# board.net
KiCad netlist of a schematic drawn in EAGLE
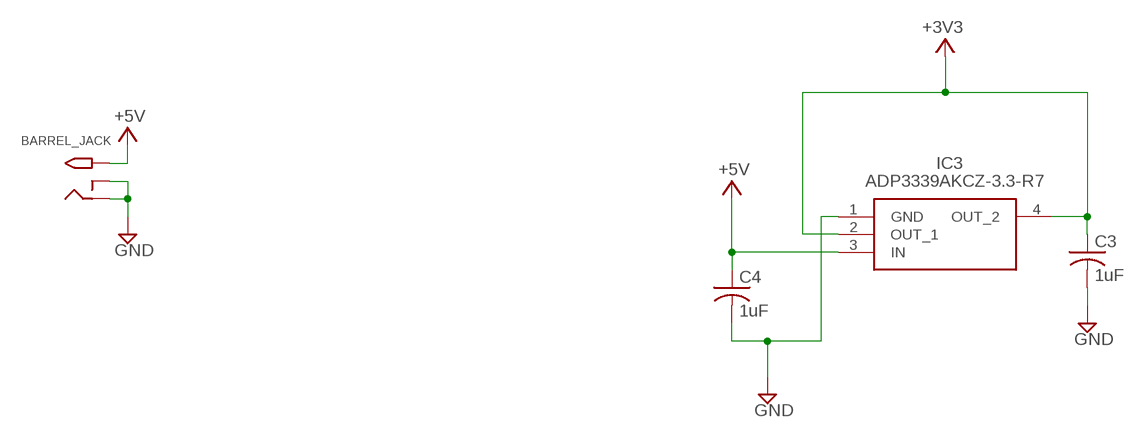
[diagram p0: schematic, sheet 1]
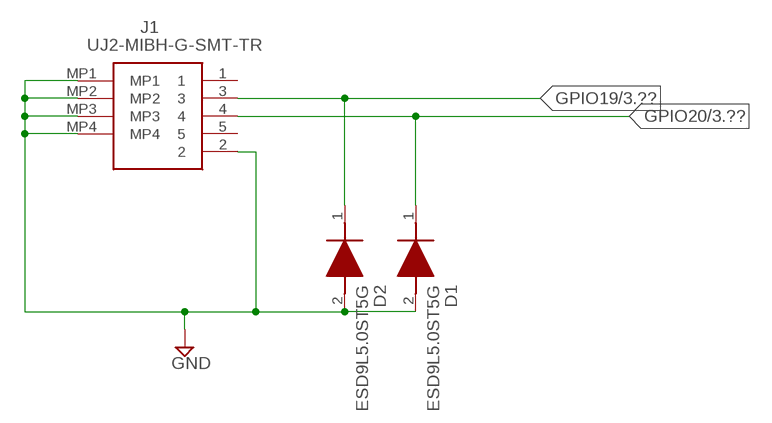
[diagram p1: schematic, sheet 2]
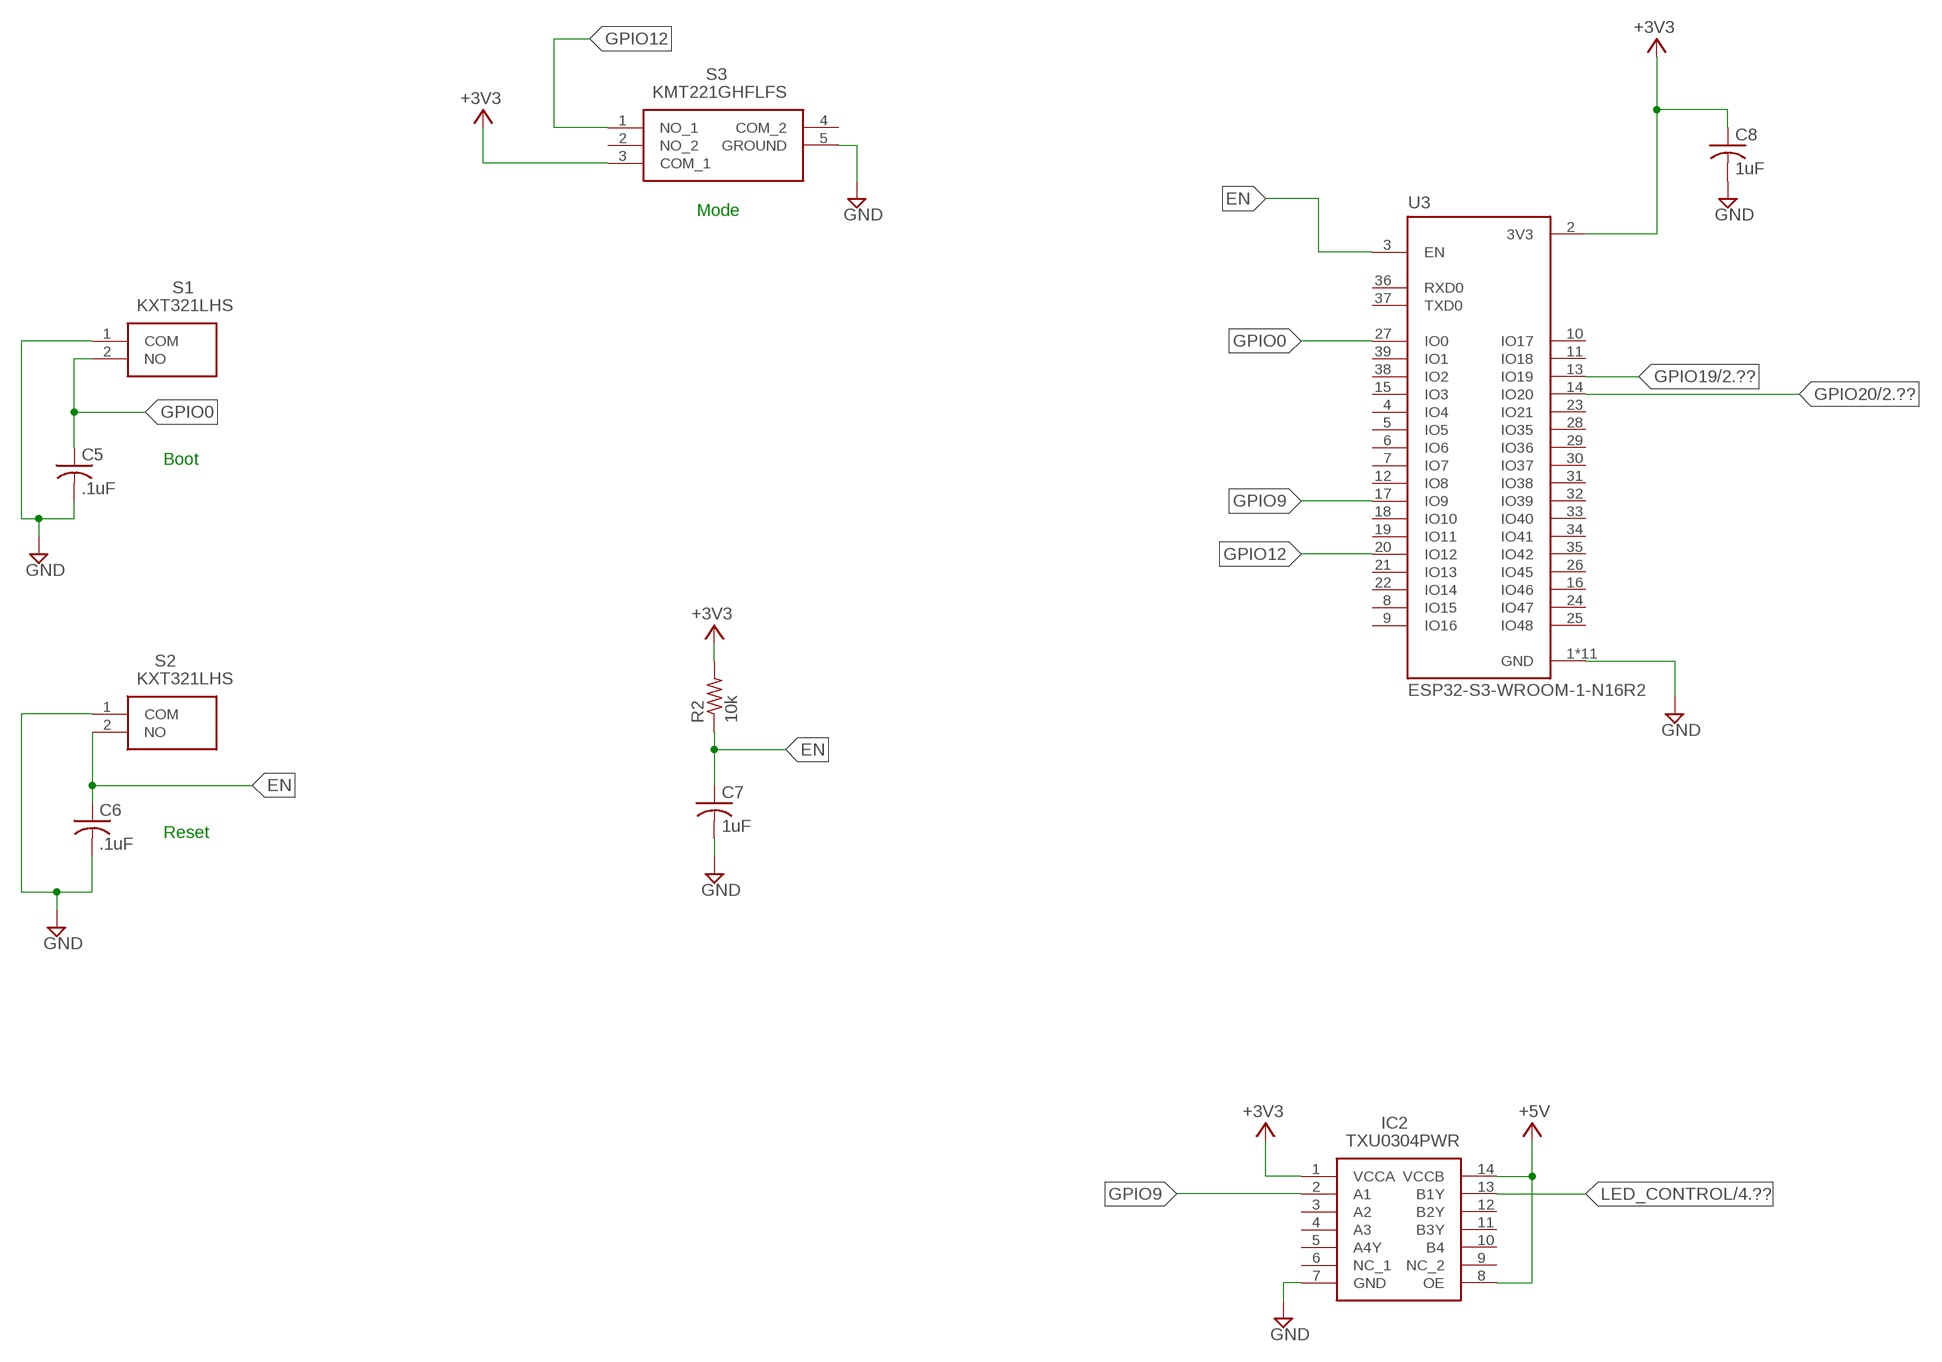
[diagram p2: schematic, sheet 3]
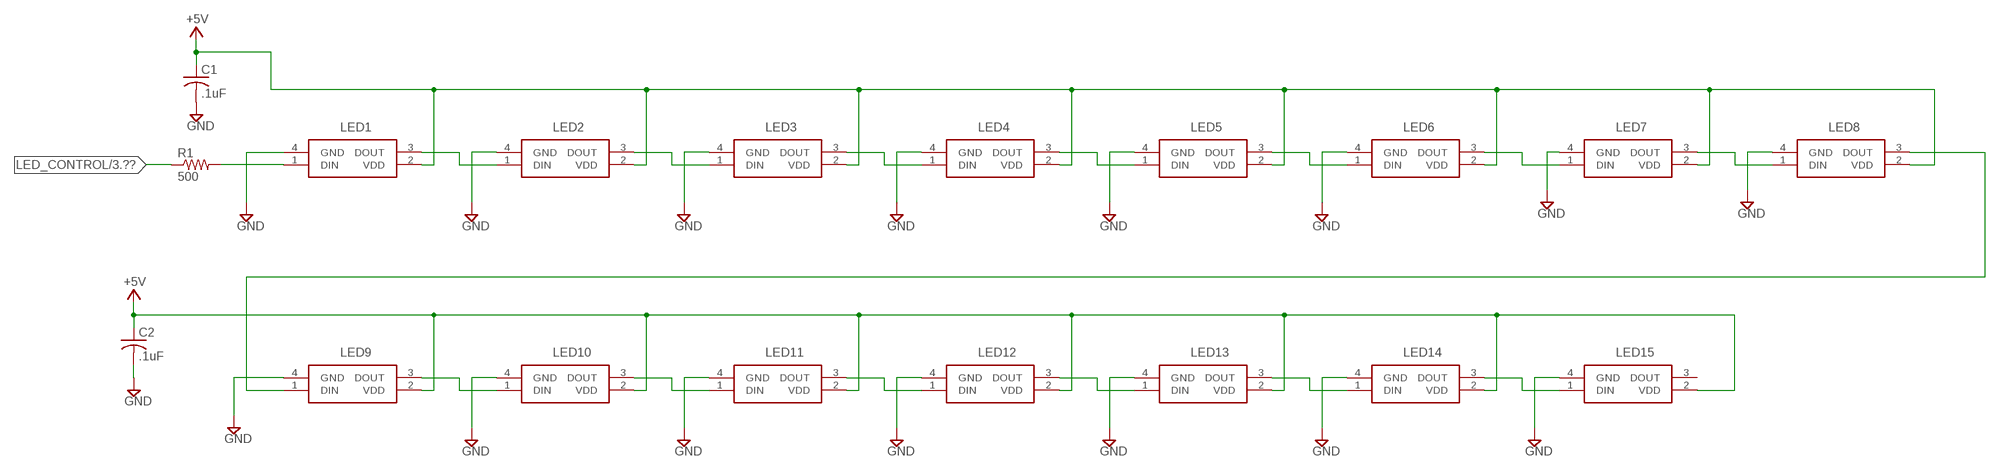
[diagram p3: schematic, sheet 4]
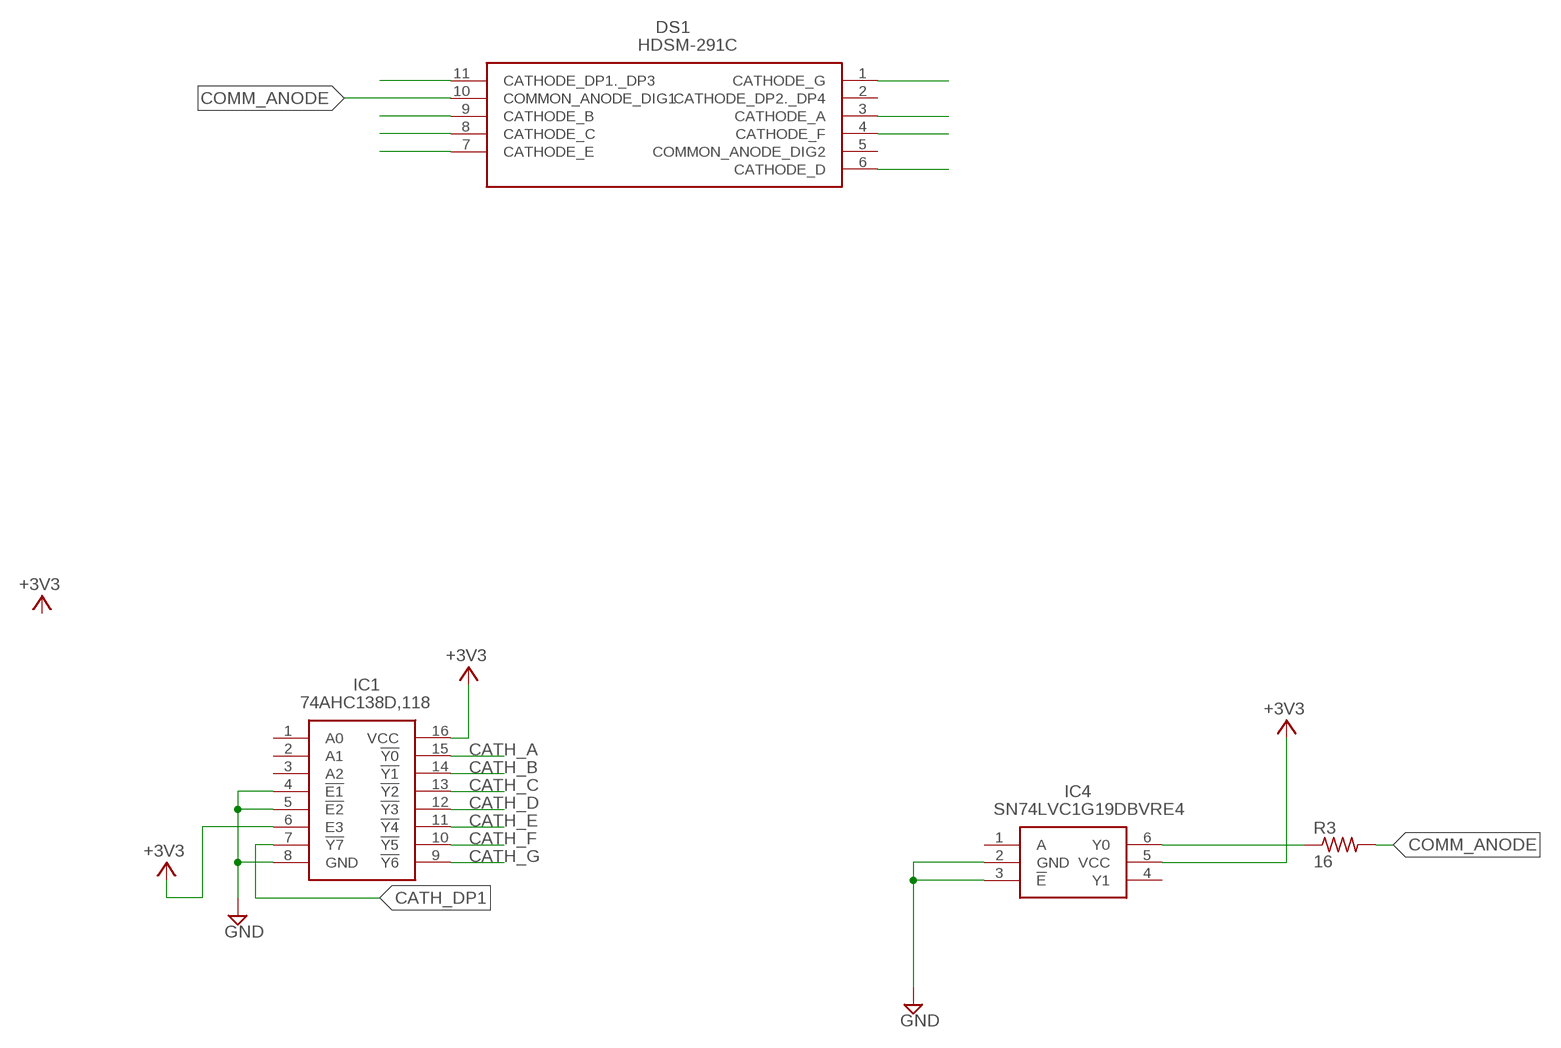
[diagram p4: schematic, sheet 5]

(export (version "E")
  (design (tool "Eeschema 10.0.6"))
  (components
    (comp (ref "BARREL_JACK")
      (value "2.1MMJACKTHM")
      (footprint "eagle-import:PJ-102A")
      (libsource (lib "eagle-import") (part "2.1MMJACKTHM"))
    )
    (comp (ref "C3")
      (value "1uF")
      (footprint "eagle-import:C0402")
      (libsource (lib "eagle-import") (part "C-USC0402"))
    )
    (comp (ref "C4")
      (value "1uF")
      (footprint "eagle-import:C0402")
      (libsource (lib "eagle-import") (part "C-USC0402"))
    )
    (comp (ref "IC3")
      (value "ADP3339AKCZ-3.3-R7")
      (footprint "eagle-import:SOT230P700X180-4N")
      (fields (field (name "MOUSER_PART_NUMBER") "584-ADP3339AKCZ3.3R7"))
      (libsource (lib "eagle-import") (part "ADP3339AKCZ-3.3-R7"))
    )
    (comp (ref "D1")
      (value "ESD9L5.0ST5G")
      (footprint "eagle-import:SODFL1006X40N")
      (fields (field (name "MOUSER_PART_NUMBER") "863-ESD9L5.0ST5G"))
      (libsource (lib "eagle-import") (part "ESD9L5.0ST5G"))
    )
    (comp (ref "D2")
      (value "ESD9L5.0ST5G")
      (footprint "eagle-import:SODFL1006X40N")
      (fields (field (name "MOUSER_PART_NUMBER") "863-ESD9L5.0ST5G"))
      (libsource (lib "eagle-import") (part "ESD9L5.0ST5G"))
    )
    (comp (ref "J1")
      (value "UJ2-MIBH-G-SMT-TR")
      (footprint "eagle-import:UJ2MIBHGSMTTR")
      (fields (field (name "MOUSER_PART_NUMBER") "490-UJ2-MIBH-G-SMTTR"))
      (libsource (lib "eagle-import") (part "UJ2-MIBH-G-SMT-TR"))
    )
    (comp (ref "C5")
      (value ".1uF")
      (footprint "eagle-import:C0402")
      (libsource (lib "eagle-import") (part "C-USC0402"))
    )
    (comp (ref "C6")
      (value ".1uF")
      (footprint "eagle-import:C0402")
      (libsource (lib "eagle-import") (part "C-USC0402"))
    )
    (comp (ref "C7")
      (value "1uF")
      (footprint "eagle-import:C0402")
      (libsource (lib "eagle-import") (part "C-USC0402"))
    )
    (comp (ref "C8")
      (value "1uF")
      (footprint "eagle-import:C0402")
      (libsource (lib "eagle-import") (part "C-USC0402"))
    )
    (comp (ref "IC2")
      (value "TXU0304PWR")
      (footprint "eagle-import:SOP65P640X120-14N")
      (fields (field (name "MOUSER_PART_NUMBER") "595-TXU0304PWR"))
      (libsource (lib "eagle-import") (part "TXU0304PWR"))
    )
    (comp (ref "R2")
      (value "10k")
      (footprint "eagle-import:R0402")
      (libsource (lib "eagle-import") (part "R-US_R0402"))
    )
    (comp (ref "S1")
      (value "KXT321LHS")
      (footprint "eagle-import:KXT321LHS")
      (fields (field (name "MOUSER_PART_NUMBER") "611-KXT321LHS"))
      (libsource (lib "eagle-import") (part "KXT321LHS"))
    )
    (comp (ref "S2")
      (value "KXT321LHS")
      (footprint "eagle-import:KXT321LHS")
      (fields (field (name "MOUSER_PART_NUMBER") "611-KXT321LHS"))
      (libsource (lib "eagle-import") (part "KXT321LHS"))
    )
    (comp (ref "S3")
      (value "KMT221GHFLFS")
      (footprint "eagle-import:KMT221GHFLFS")
      (fields (field (name "MOUSER_PART_NUMBER") "611-KMT221GHFLFS"))
      (libsource (lib "eagle-import") (part "KMT221GHFLFS"))
    )
    (comp (ref "U3")
      (value "ESP32-S3-WROOM-1-N16R2")
      (footprint "eagle-import:XCVR_ESP32-S3-WROOM-1-N16R2")
      (fields (field (name "MF") "Espressif Systems"))
      (libsource (lib "eagle-import") (part "ESP32-S3-WROOM-1-N16R2"))
    )
    (comp (ref "DS1")
      (value "HDSM-291C")
      (footprint "eagle-import:HDSM283L")
      (fields (field (name "MOUSER_PART_NUMBER") "630-HDSM-291C"))
      (libsource (lib "eagle-import") (part "HDSM-291C"))
    )
    (comp (ref "IC1")
      (value "74AHC138D,118")
      (footprint "eagle-import:SOIC127P600X175-16N")
      (fields (field (name "MOUSER_PART_NUMBER") "771-74AHC138D-T"))
      (libsource (lib "eagle-import") (part "74AHC138D,118"))
    )
    (comp (ref "IC4")
      (value "SN74LVC1G19DBVRE4")
      (footprint "eagle-import:SOT95P280X145-6N")
      (fields (field (name "MOUSER_PART_NUMBER") "595-74LVC1G19DBVRE4"))
      (libsource (lib "eagle-import") (part "SN74LVC1G19DBVRE4"))
    )
    (comp (ref "R3")
      (value "16")
      (footprint "eagle-import:R0402")
      (libsource (lib "eagle-import") (part "R-US_R0402"))
    )
    (comp (ref "C1")
      (value ".1uF")
      (footprint "eagle-import:C0402")
      (libsource (lib "eagle-import") (part "C-USC0402"))
    )
    (comp (ref "C2")
      (value ".1uF")
      (footprint "eagle-import:C0402")
      (libsource (lib "eagle-import") (part "C-USC0402"))
    )
    (comp (ref "LED1")
      (value "4492__SK6805-EC_15_")
      (footprint "eagle-import:4492SK6805EC15")
      (fields (field (name "MANUFACTURER_PART_NUMBER") "4492 (SK6805-EC 15)"))
      (libsource (lib "eagle-import") (part "4492__SK6805-EC_15_"))
    )
    (comp (ref "LED2")
      (value "4492__SK6805-EC_15_")
      (footprint "eagle-import:4492SK6805EC15")
      (fields (field (name "MANUFACTURER_PART_NUMBER") "4492 (SK6805-EC 15)"))
      (libsource (lib "eagle-import") (part "4492__SK6805-EC_15_"))
    )
    (comp (ref "LED3")
      (value "4492__SK6805-EC_15_")
      (footprint "eagle-import:4492SK6805EC15")
      (fields (field (name "MANUFACTURER_PART_NUMBER") "4492 (SK6805-EC 15)"))
      (libsource (lib "eagle-import") (part "4492__SK6805-EC_15_"))
    )
    (comp (ref "LED4")
      (value "4492__SK6805-EC_15_")
      (footprint "eagle-import:4492SK6805EC15")
      (fields (field (name "MANUFACTURER_PART_NUMBER") "4492 (SK6805-EC 15)"))
      (libsource (lib "eagle-import") (part "4492__SK6805-EC_15_"))
    )
    (comp (ref "LED5")
      (value "4492__SK6805-EC_15_")
      (footprint "eagle-import:4492SK6805EC15")
      (fields (field (name "MANUFACTURER_PART_NUMBER") "4492 (SK6805-EC 15)"))
      (libsource (lib "eagle-import") (part "4492__SK6805-EC_15_"))
    )
    (comp (ref "LED6")
      (value "4492__SK6805-EC_15_")
      (footprint "eagle-import:4492SK6805EC15")
      (fields (field (name "MANUFACTURER_PART_NUMBER") "4492 (SK6805-EC 15)"))
      (libsource (lib "eagle-import") (part "4492__SK6805-EC_15_"))
    )
    (comp (ref "LED7")
      (value "4492__SK6805-EC_15_")
      (footprint "eagle-import:4492SK6805EC15")
      (fields (field (name "MANUFACTURER_PART_NUMBER") "4492 (SK6805-EC 15)"))
      (libsource (lib "eagle-import") (part "4492__SK6805-EC_15_"))
    )
    (comp (ref "LED8")
      (value "4492__SK6805-EC_15_")
      (footprint "eagle-import:4492SK6805EC15")
      (fields (field (name "MANUFACTURER_PART_NUMBER") "4492 (SK6805-EC 15)"))
      (libsource (lib "eagle-import") (part "4492__SK6805-EC_15_"))
    )
    (comp (ref "LED9")
      (value "4492__SK6805-EC_15_")
      (footprint "eagle-import:4492SK6805EC15")
      (fields (field (name "MANUFACTURER_PART_NUMBER") "4492 (SK6805-EC 15)"))
      (libsource (lib "eagle-import") (part "4492__SK6805-EC_15_"))
    )
    (comp (ref "LED10")
      (value "4492__SK6805-EC_15_")
      (footprint "eagle-import:4492SK6805EC15")
      (fields (field (name "MANUFACTURER_PART_NUMBER") "4492 (SK6805-EC 15)"))
      (libsource (lib "eagle-import") (part "4492__SK6805-EC_15_"))
    )
    (comp (ref "LED11")
      (value "4492__SK6805-EC_15_")
      (footprint "eagle-import:4492SK6805EC15")
      (fields (field (name "MANUFACTURER_PART_NUMBER") "4492 (SK6805-EC 15)"))
      (libsource (lib "eagle-import") (part "4492__SK6805-EC_15_"))
    )
    (comp (ref "LED12")
      (value "4492__SK6805-EC_15_")
      (footprint "eagle-import:4492SK6805EC15")
      (fields (field (name "MANUFACTURER_PART_NUMBER") "4492 (SK6805-EC 15)"))
      (libsource (lib "eagle-import") (part "4492__SK6805-EC_15_"))
    )
    (comp (ref "LED13")
      (value "4492__SK6805-EC_15_")
      (footprint "eagle-import:4492SK6805EC15")
      (fields (field (name "MANUFACTURER_PART_NUMBER") "4492 (SK6805-EC 15)"))
      (libsource (lib "eagle-import") (part "4492__SK6805-EC_15_"))
    )
    (comp (ref "LED14")
      (value "4492__SK6805-EC_15_")
      (footprint "eagle-import:4492SK6805EC15")
      (fields (field (name "MANUFACTURER_PART_NUMBER") "4492 (SK6805-EC 15)"))
      (libsource (lib "eagle-import") (part "4492__SK6805-EC_15_"))
    )
    (comp (ref "LED15")
      (value "4492__SK6805-EC_15_")
      (footprint "eagle-import:4492SK6805EC15")
      (fields (field (name "MANUFACTURER_PART_NUMBER") "4492 (SK6805-EC 15)"))
      (libsource (lib "eagle-import") (part "4492__SK6805-EC_15_"))
    )
    (comp (ref "R1")
      (value "500")
      (footprint "eagle-import:R0402")
      (libsource (lib "eagle-import") (part "R-US_R0402"))
    )
  )
  (nets
    (net (code "1") (name "+3V3") (class "Default")
      (node (ref "C3") (pin "1") (pinfunction "1_1") (pintype "passive"))
      (node (ref "C8") (pin "1") (pinfunction "1_1") (pintype "passive"))
      (node (ref "IC1") (pin "16") (pinfunction "VCC_16") (pintype "bidirectional"))
      (node (ref "IC1") (pin "6") (pinfunction "E3_6") (pintype "bidirectional"))
      (node (ref "IC2") (pin "1") (pinfunction "VCCA_1") (pintype "bidirectional"))
      (node (ref "IC3") (pin "2") (pinfunction "OUT_1_2") (pintype "bidirectional"))
      (node (ref "IC3") (pin "4") (pinfunction "OUT_2_4") (pintype "bidirectional"))
      (node (ref "IC4") (pin "5") (pinfunction "VCC_5") (pintype "bidirectional"))
      (node (ref "R2") (pin "2") (pinfunction "2_2") (pintype "passive"))
      (node (ref "S3") (pin "3") (pinfunction "COM_1_3") (pintype "bidirectional"))
      (node (ref "U3") (pin "2") (pinfunction "3V3_2") (pintype "power_in"))
    )
    (net (code "2") (name "+5V") (class "Default")
      (node (ref "BARREL_JACK") (pin "TIP") (pinfunction "TIP_TIP") (pintype "bidirectional"))
      (node (ref "C1") (pin "1") (pinfunction "1_1") (pintype "passive"))
      (node (ref "C2") (pin "1") (pinfunction "1_1") (pintype "passive"))
      (node (ref "C4") (pin "1") (pinfunction "1_1") (pintype "passive"))
      (node (ref "IC2") (pin "14") (pinfunction "VCCB_14") (pintype "bidirectional"))
      (node (ref "IC2") (pin "8") (pinfunction "OE_8") (pintype "bidirectional"))
      (node (ref "IC3") (pin "3") (pinfunction "IN_3") (pintype "bidirectional"))
      (node (ref "LED1") (pin "2") (pinfunction "VDD_2") (pintype "bidirectional"))
      (node (ref "LED10") (pin "2") (pinfunction "VDD_2") (pintype "bidirectional"))
      (node (ref "LED11") (pin "2") (pinfunction "VDD_2") (pintype "bidirectional"))
      (node (ref "LED12") (pin "2") (pinfunction "VDD_2") (pintype "bidirectional"))
      (node (ref "LED13") (pin "2") (pinfunction "VDD_2") (pintype "bidirectional"))
      (node (ref "LED14") (pin "2") (pinfunction "VDD_2") (pintype "bidirectional"))
      (node (ref "LED15") (pin "2") (pinfunction "VDD_2") (pintype "bidirectional"))
      (node (ref "LED2") (pin "2") (pinfunction "VDD_2") (pintype "bidirectional"))
      (node (ref "LED3") (pin "2") (pinfunction "VDD_2") (pintype "bidirectional"))
      (node (ref "LED4") (pin "2") (pinfunction "VDD_2") (pintype "bidirectional"))
      (node (ref "LED5") (pin "2") (pinfunction "VDD_2") (pintype "bidirectional"))
      (node (ref "LED6") (pin "2") (pinfunction "VDD_2") (pintype "bidirectional"))
      (node (ref "LED7") (pin "2") (pinfunction "VDD_2") (pintype "bidirectional"))
      (node (ref "LED8") (pin "2") (pinfunction "VDD_2") (pintype "bidirectional"))
      (node (ref "LED9") (pin "2") (pinfunction "VDD_2") (pintype "bidirectional"))
    )
    (net (code "3") (name "CATH_A") (class "Default")
      (node (ref "IC1") (pin "15") (pinfunction "~{Y0}_15") (pintype "bidirectional"))
    )
    (net (code "4") (name "CATH_B") (class "Default")
      (node (ref "IC1") (pin "14") (pinfunction "~{Y1}_14") (pintype "bidirectional"))
    )
    (net (code "5") (name "CATH_C") (class "Default")
      (node (ref "IC1") (pin "13") (pinfunction "~{Y2}_13") (pintype "bidirectional"))
    )
    (net (code "6") (name "CATH_D") (class "Default")
      (node (ref "IC1") (pin "12") (pinfunction "~{Y3}_12") (pintype "bidirectional"))
    )
    (net (code "7") (name "CATH_DP1") (class "Default")
      (node (ref "IC1") (pin "7") (pinfunction "~{Y7}_7") (pintype "bidirectional"))
    )
    (net (code "8") (name "CATH_E") (class "Default")
      (node (ref "IC1") (pin "11") (pinfunction "~{Y4}_11") (pintype "bidirectional"))
    )
    (net (code "9") (name "CATH_F") (class "Default")
      (node (ref "IC1") (pin "10") (pinfunction "~{Y5}_10") (pintype "bidirectional"))
    )
    (net (code "10") (name "CATH_G") (class "Default")
      (node (ref "IC1") (pin "9") (pinfunction "~{Y6}_9") (pintype "bidirectional"))
    )
    (net (code "11") (name "COMM_ANODE") (class "Default")
      (node (ref "DS1") (pin "10") (pinfunction "COMMON_ANODE_DIG1_10") (pintype "bidirectional"))
      (node (ref "R3") (pin "2") (pinfunction "2_2") (pintype "passive"))
    )
    (net (code "12") (name "EN") (class "Default")
      (node (ref "C6") (pin "1") (pinfunction "1_1") (pintype "passive"))
      (node (ref "C7") (pin "1") (pinfunction "1_1") (pintype "passive"))
      (node (ref "R2") (pin "1") (pinfunction "1_1") (pintype "passive"))
      (node (ref "S2") (pin "2") (pinfunction "NO_2") (pintype "bidirectional"))
      (node (ref "U3") (pin "3") (pinfunction "EN_3") (pintype "input"))
    )
    (net (code "13") (name "GND") (class "Default")
      (node (ref "BARREL_JACK") (pin "RING") (pinfunction "RING_RING") (pintype "bidirectional"))
      (node (ref "BARREL_JACK") (pin "RING_SW") (pinfunction "RING_SW_RING_SW") (pintype "bidirectional"))
      (node (ref "C1") (pin "2") (pinfunction "2_2") (pintype "passive"))
      (node (ref "C2") (pin "2") (pinfunction "2_2") (pintype "passive"))
      (node (ref "C3") (pin "2") (pinfunction "2_2") (pintype "passive"))
      (node (ref "C4") (pin "2") (pinfunction "2_2") (pintype "passive"))
      (node (ref "C5") (pin "2") (pinfunction "2_2") (pintype "passive"))
      (node (ref "C6") (pin "2") (pinfunction "2_2") (pintype "passive"))
      (node (ref "C7") (pin "2") (pinfunction "2_2") (pintype "passive"))
      (node (ref "C8") (pin "2") (pinfunction "2_2") (pintype "passive"))
      (node (ref "D1") (pin "2") (pinfunction "A_2") (pintype "bidirectional"))
      (node (ref "D2") (pin "2") (pinfunction "A_2") (pintype "bidirectional"))
      (node (ref "IC1") (pin "4") (pinfunction "~{E1}_4") (pintype "bidirectional"))
      (node (ref "IC1") (pin "5") (pinfunction "~{E2}_5") (pintype "bidirectional"))
      (node (ref "IC1") (pin "8") (pinfunction "GND_8") (pintype "bidirectional"))
      (node (ref "IC2") (pin "7") (pinfunction "GND_7") (pintype "bidirectional"))
      (node (ref "IC3") (pin "1") (pinfunction "GND_1") (pintype "bidirectional"))
      (node (ref "IC4") (pin "2") (pinfunction "GND_2") (pintype "bidirectional"))
      (node (ref "IC4") (pin "3") (pinfunction "~{E}_3") (pintype "bidirectional"))
      (node (ref "J1") (pin "2") (pinfunction "2_2") (pintype "bidirectional"))
      (node (ref "J1") (pin "MP1") (pinfunction "MP1_MP1") (pintype "bidirectional"))
      (node (ref "J1") (pin "MP2") (pinfunction "MP2_MP2") (pintype "bidirectional"))
      (node (ref "J1") (pin "MP3") (pinfunction "MP3_MP3") (pintype "bidirectional"))
      (node (ref "J1") (pin "MP4") (pinfunction "MP4_MP4") (pintype "bidirectional"))
      (node (ref "LED1") (pin "4") (pinfunction "GND_4") (pintype "bidirectional"))
      (node (ref "LED10") (pin "4") (pinfunction "GND_4") (pintype "bidirectional"))
      (node (ref "LED11") (pin "4") (pinfunction "GND_4") (pintype "bidirectional"))
      (node (ref "LED12") (pin "4") (pinfunction "GND_4") (pintype "bidirectional"))
      (node (ref "LED13") (pin "4") (pinfunction "GND_4") (pintype "bidirectional"))
      (node (ref "LED14") (pin "4") (pinfunction "GND_4") (pintype "bidirectional"))
      (node (ref "LED15") (pin "4") (pinfunction "GND_4") (pintype "bidirectional"))
      (node (ref "LED2") (pin "4") (pinfunction "GND_4") (pintype "bidirectional"))
      (node (ref "LED3") (pin "4") (pinfunction "GND_4") (pintype "bidirectional"))
      (node (ref "LED4") (pin "4") (pinfunction "GND_4") (pintype "bidirectional"))
      (node (ref "LED5") (pin "4") (pinfunction "GND_4") (pintype "bidirectional"))
      (node (ref "LED6") (pin "4") (pinfunction "GND_4") (pintype "bidirectional"))
      (node (ref "LED7") (pin "4") (pinfunction "GND_4") (pintype "bidirectional"))
      (node (ref "LED8") (pin "4") (pinfunction "GND_4") (pintype "bidirectional"))
      (node (ref "LED9") (pin "4") (pinfunction "GND_4") (pintype "bidirectional"))
      (node (ref "S1") (pin "1") (pinfunction "COM_1") (pintype "bidirectional"))
      (node (ref "S2") (pin "1") (pinfunction "COM_1") (pintype "bidirectional"))
      (node (ref "S3") (pin "5") (pinfunction "GROUND_5") (pintype "bidirectional"))
      (node (ref "U3") (pin "1") (pinfunction "GND_1") (pintype "power_in"))
      (node (ref "U3") (pin "40") (pinfunction "GND_40") (pintype "power_in"))
      (node (ref "U3") (pin "41_1") (pinfunction "GND_41_1") (pintype "power_in"))
      (node (ref "U3") (pin "41_2") (pinfunction "GND_41_2") (pintype "power_in"))
      (node (ref "U3") (pin "41_3") (pinfunction "GND_41_3") (pintype "power_in"))
      (node (ref "U3") (pin "41_4") (pinfunction "GND_41_4") (pintype "power_in"))
      (node (ref "U3") (pin "41_5") (pinfunction "GND_41_5") (pintype "power_in"))
      (node (ref "U3") (pin "41_6") (pinfunction "GND_41_6") (pintype "power_in"))
      (node (ref "U3") (pin "41_7") (pinfunction "GND_41_7") (pintype "power_in"))
      (node (ref "U3") (pin "41_8") (pinfunction "GND_41_8") (pintype "power_in"))
      (node (ref "U3") (pin "41_9") (pinfunction "GND_41_9") (pintype "power_in"))
    )
    (net (code "14") (name "GPIO0") (class "Default")
      (node (ref "C5") (pin "1") (pinfunction "1_1") (pintype "passive"))
      (node (ref "S1") (pin "2") (pinfunction "NO_2") (pintype "bidirectional"))
      (node (ref "U3") (pin "27") (pinfunction "IO0_27") (pintype "bidirectional"))
    )
    (net (code "15") (name "GPIO9") (class "Default")
      (node (ref "IC2") (pin "2") (pinfunction "A1_2") (pintype "bidirectional"))
      (node (ref "U3") (pin "17") (pinfunction "IO9_17") (pintype "bidirectional"))
    )
    (net (code "16") (name "GPIO12") (class "Default")
      (node (ref "S3") (pin "1") (pinfunction "NO_1_1") (pintype "bidirectional"))
      (node (ref "U3") (pin "20") (pinfunction "IO12_20") (pintype "bidirectional"))
    )
    (net (code "17") (name "GPIO19") (class "Default")
      (node (ref "D2") (pin "1") (pinfunction "K_1") (pintype "bidirectional"))
      (node (ref "J1") (pin "3") (pinfunction "3_3") (pintype "bidirectional"))
      (node (ref "U3") (pin "13") (pinfunction "IO19_13") (pintype "bidirectional"))
    )
    (net (code "18") (name "GPIO20") (class "Default")
      (node (ref "D1") (pin "1") (pinfunction "K_1") (pintype "bidirectional"))
      (node (ref "J1") (pin "4") (pinfunction "4_4") (pintype "bidirectional"))
      (node (ref "U3") (pin "14") (pinfunction "IO20_14") (pintype "bidirectional"))
    )
    (net (code "19") (name "LED_CONTROL") (class "Default")
      (node (ref "IC2") (pin "13") (pinfunction "B1Y_13") (pintype "bidirectional"))
      (node (ref "R1") (pin "1") (pinfunction "1_1") (pintype "passive"))
    )
    (net (code "20") (name "Net-(IC4-Y0)") (class "Default")
      (node (ref "IC4") (pin "6") (pinfunction "Y0_6") (pintype "bidirectional"))
      (node (ref "R3") (pin "1") (pinfunction "1_1") (pintype "passive"))
    )
    (net (code "21") (name "Net-(LED1-DIN)") (class "Default")
      (node (ref "LED1") (pin "1") (pinfunction "DIN_1") (pintype "bidirectional"))
      (node (ref "R1") (pin "2") (pinfunction "2_2") (pintype "passive"))
    )
    (net (code "22") (name "Net-(LED1-DOUT)") (class "Default")
      (node (ref "LED1") (pin "3") (pinfunction "DOUT_3") (pintype "bidirectional"))
      (node (ref "LED2") (pin "1") (pinfunction "DIN_1") (pintype "bidirectional"))
    )
    (net (code "23") (name "Net-(LED2-DOUT)") (class "Default")
      (node (ref "LED2") (pin "3") (pinfunction "DOUT_3") (pintype "bidirectional"))
      (node (ref "LED3") (pin "1") (pinfunction "DIN_1") (pintype "bidirectional"))
    )
    (net (code "24") (name "Net-(LED3-DOUT)") (class "Default")
      (node (ref "LED3") (pin "3") (pinfunction "DOUT_3") (pintype "bidirectional"))
      (node (ref "LED4") (pin "1") (pinfunction "DIN_1") (pintype "bidirectional"))
    )
    (net (code "25") (name "Net-(LED4-DOUT)") (class "Default")
      (node (ref "LED4") (pin "3") (pinfunction "DOUT_3") (pintype "bidirectional"))
      (node (ref "LED5") (pin "1") (pinfunction "DIN_1") (pintype "bidirectional"))
    )
    (net (code "26") (name "Net-(LED5-DOUT)") (class "Default")
      (node (ref "LED5") (pin "3") (pinfunction "DOUT_3") (pintype "bidirectional"))
      (node (ref "LED6") (pin "1") (pinfunction "DIN_1") (pintype "bidirectional"))
    )
    (net (code "27") (name "Net-(LED6-DOUT)") (class "Default")
      (node (ref "LED6") (pin "3") (pinfunction "DOUT_3") (pintype "bidirectional"))
      (node (ref "LED7") (pin "1") (pinfunction "DIN_1") (pintype "bidirectional"))
    )
    (net (code "28") (name "Net-(LED7-DOUT)") (class "Default")
      (node (ref "LED7") (pin "3") (pinfunction "DOUT_3") (pintype "bidirectional"))
      (node (ref "LED8") (pin "1") (pinfunction "DIN_1") (pintype "bidirectional"))
    )
    (net (code "29") (name "Net-(LED8-DOUT)") (class "Default")
      (node (ref "LED8") (pin "3") (pinfunction "DOUT_3") (pintype "bidirectional"))
      (node (ref "LED9") (pin "1") (pinfunction "DIN_1") (pintype "bidirectional"))
    )
    (net (code "30") (name "Net-(LED10-DIN)") (class "Default")
      (node (ref "LED10") (pin "1") (pinfunction "DIN_1") (pintype "bidirectional"))
      (node (ref "LED9") (pin "3") (pinfunction "DOUT_3") (pintype "bidirectional"))
    )
    (net (code "31") (name "Net-(LED10-DOUT)") (class "Default")
      (node (ref "LED10") (pin "3") (pinfunction "DOUT_3") (pintype "bidirectional"))
      (node (ref "LED11") (pin "1") (pinfunction "DIN_1") (pintype "bidirectional"))
    )
    (net (code "32") (name "Net-(LED11-DOUT)") (class "Default")
      (node (ref "LED11") (pin "3") (pinfunction "DOUT_3") (pintype "bidirectional"))
      (node (ref "LED12") (pin "1") (pinfunction "DIN_1") (pintype "bidirectional"))
    )
    (net (code "33") (name "Net-(LED12-DOUT)") (class "Default")
      (node (ref "LED12") (pin "3") (pinfunction "DOUT_3") (pintype "bidirectional"))
      (node (ref "LED13") (pin "1") (pinfunction "DIN_1") (pintype "bidirectional"))
    )
    (net (code "34") (name "Net-(LED13-DOUT)") (class "Default")
      (node (ref "LED13") (pin "3") (pinfunction "DOUT_3") (pintype "bidirectional"))
      (node (ref "LED14") (pin "1") (pinfunction "DIN_1") (pintype "bidirectional"))
    )
    (net (code "35") (name "Net-(LED14-DOUT)") (class "Default")
      (node (ref "LED14") (pin "3") (pinfunction "DOUT_3") (pintype "bidirectional"))
      (node (ref "LED15") (pin "1") (pinfunction "DIN_1") (pintype "bidirectional"))
    )
    (net (code "36") (name "unconnected-(DS1-CATHODE_A-Pad3)") (class "Default")
      (node (ref "DS1") (pin "3") (pinfunction "CATHODE_A_3") (pintype "bidirectional"))
    )
    (net (code "37") (name "unconnected-(DS1-CATHODE_B-Pad9)") (class "Default")
      (node (ref "DS1") (pin "9") (pinfunction "CATHODE_B_9") (pintype "bidirectional"))
    )
    (net (code "38") (name "unconnected-(DS1-CATHODE_C-Pad8)") (class "Default")
      (node (ref "DS1") (pin "8") (pinfunction "CATHODE_C_8") (pintype "bidirectional"))
    )
    (net (code "39") (name "unconnected-(DS1-CATHODE_D-Pad6)") (class "Default")
      (node (ref "DS1") (pin "6") (pinfunction "CATHODE_D_6") (pintype "bidirectional"))
    )
    (net (code "40") (name "unconnected-(DS1-CATHODE_DP1._DP3-Pad11)") (class "Default")
      (node (ref "DS1") (pin "11") (pinfunction "CATHODE_DP1._DP3_11") (pintype "bidirectional"))
    )
    (net (code "41") (name "unconnected-(DS1-CATHODE_DP2._DP4-Pad2)") (class "Default")
      (node (ref "DS1") (pin "2") (pinfunction "CATHODE_DP2._DP4_2") (pintype "bidirectional"))
    )
    (net (code "42") (name "unconnected-(DS1-CATHODE_E-Pad7)") (class "Default")
      (node (ref "DS1") (pin "7") (pinfunction "CATHODE_E_7") (pintype "bidirectional"))
    )
    (net (code "43") (name "unconnected-(DS1-CATHODE_F-Pad4)") (class "Default")
      (node (ref "DS1") (pin "4") (pinfunction "CATHODE_F_4") (pintype "bidirectional"))
    )
    (net (code "44") (name "unconnected-(DS1-CATHODE_G-Pad1)") (class "Default")
      (node (ref "DS1") (pin "1") (pinfunction "CATHODE_G_1") (pintype "bidirectional"))
    )
    (net (code "45") (name "unconnected-(DS1-COMMON_ANODE_DIG2-Pad5)") (class "Default")
      (node (ref "DS1") (pin "5") (pinfunction "COMMON_ANODE_DIG2_5") (pintype "bidirectional"))
    )
    (net (code "46") (name "unconnected-(IC1-A0-Pad1)") (class "Default")
      (node (ref "IC1") (pin "1") (pinfunction "A0_1") (pintype "bidirectional"))
    )
    (net (code "47") (name "unconnected-(IC1-A1-Pad2)") (class "Default")
      (node (ref "IC1") (pin "2") (pinfunction "A1_2") (pintype "bidirectional"))
    )
    (net (code "48") (name "unconnected-(IC1-A2-Pad3)") (class "Default")
      (node (ref "IC1") (pin "3") (pinfunction "A2_3") (pintype "bidirectional"))
    )
    (net (code "49") (name "unconnected-(IC2-A2-Pad3)") (class "Default")
      (node (ref "IC2") (pin "3") (pinfunction "A2_3") (pintype "bidirectional"))
    )
    (net (code "50") (name "unconnected-(IC2-A3-Pad4)") (class "Default")
      (node (ref "IC2") (pin "4") (pinfunction "A3_4") (pintype "bidirectional"))
    )
    (net (code "51") (name "unconnected-(IC2-A4Y-Pad5)") (class "Default")
      (node (ref "IC2") (pin "5") (pinfunction "A4Y_5") (pintype "bidirectional"))
    )
    (net (code "52") (name "unconnected-(IC2-B2Y-Pad12)") (class "Default")
      (node (ref "IC2") (pin "12") (pinfunction "B2Y_12") (pintype "bidirectional"))
    )
    (net (code "53") (name "unconnected-(IC2-B3Y-Pad11)") (class "Default")
      (node (ref "IC2") (pin "11") (pinfunction "B3Y_11") (pintype "bidirectional"))
    )
    (net (code "54") (name "unconnected-(IC2-B4-Pad10)") (class "Default")
      (node (ref "IC2") (pin "10") (pinfunction "B4_10") (pintype "bidirectional"))
    )
    (net (code "55") (name "unconnected-(IC2-NC_1-Pad6)") (class "Default")
      (node (ref "IC2") (pin "6") (pinfunction "NC_1_6") (pintype "bidirectional"))
    )
    (net (code "56") (name "unconnected-(IC2-NC_2-Pad9)") (class "Default")
      (node (ref "IC2") (pin "9") (pinfunction "NC_2_9") (pintype "bidirectional"))
    )
    (net (code "57") (name "unconnected-(IC4-A-Pad1)") (class "Default")
      (node (ref "IC4") (pin "1") (pinfunction "A_1") (pintype "bidirectional"))
    )
    (net (code "58") (name "unconnected-(IC4-Y1-Pad4)") (class "Default")
      (node (ref "IC4") (pin "4") (pinfunction "Y1_4") (pintype "bidirectional"))
    )
    (net (code "59") (name "unconnected-(J1-Pad1)") (class "Default")
      (node (ref "J1") (pin "1") (pinfunction "1_1") (pintype "bidirectional"))
    )
    (net (code "60") (name "unconnected-(J1-Pad5)") (class "Default")
      (node (ref "J1") (pin "5") (pinfunction "5_5") (pintype "bidirectional"))
    )
    (net (code "61") (name "unconnected-(LED15-DOUT-Pad3)") (class "Default")
      (node (ref "LED15") (pin "3") (pinfunction "DOUT_3") (pintype "bidirectional"))
    )
    (net (code "62") (name "unconnected-(S3-COM_2-Pad4)") (class "Default")
      (node (ref "S3") (pin "4") (pinfunction "COM_2_4") (pintype "bidirectional"))
    )
    (net (code "63") (name "unconnected-(S3-NO_2-Pad2)") (class "Default")
      (node (ref "S3") (pin "2") (pinfunction "NO_2_2") (pintype "bidirectional"))
    )
    (net (code "64") (name "unconnected-(U3-IO1-Pad39)") (class "Default")
      (node (ref "U3") (pin "39") (pinfunction "IO1_39") (pintype "bidirectional"))
    )
    (net (code "65") (name "unconnected-(U3-IO2-Pad38)") (class "Default")
      (node (ref "U3") (pin "38") (pinfunction "IO2_38") (pintype "bidirectional"))
    )
    (net (code "66") (name "unconnected-(U3-IO3-Pad15)") (class "Default")
      (node (ref "U3") (pin "15") (pinfunction "IO3_15") (pintype "bidirectional"))
    )
    (net (code "67") (name "unconnected-(U3-IO4-Pad4)") (class "Default")
      (node (ref "U3") (pin "4") (pinfunction "IO4_4") (pintype "bidirectional"))
    )
    (net (code "68") (name "unconnected-(U3-IO5-Pad5)") (class "Default")
      (node (ref "U3") (pin "5") (pinfunction "IO5_5") (pintype "bidirectional"))
    )
    (net (code "69") (name "unconnected-(U3-IO6-Pad6)") (class "Default")
      (node (ref "U3") (pin "6") (pinfunction "IO6_6") (pintype "bidirectional"))
    )
    (net (code "70") (name "unconnected-(U3-IO7-Pad7)") (class "Default")
      (node (ref "U3") (pin "7") (pinfunction "IO7_7") (pintype "bidirectional"))
    )
    (net (code "71") (name "unconnected-(U3-IO8-Pad12)") (class "Default")
      (node (ref "U3") (pin "12") (pinfunction "IO8_12") (pintype "bidirectional"))
    )
    (net (code "72") (name "unconnected-(U3-IO10-Pad18)") (class "Default")
      (node (ref "U3") (pin "18") (pinfunction "IO10_18") (pintype "bidirectional"))
    )
    (net (code "73") (name "unconnected-(U3-IO11-Pad19)") (class "Default")
      (node (ref "U3") (pin "19") (pinfunction "IO11_19") (pintype "bidirectional"))
    )
    (net (code "74") (name "unconnected-(U3-IO13-Pad21)") (class "Default")
      (node (ref "U3") (pin "21") (pinfunction "IO13_21") (pintype "bidirectional"))
    )
    (net (code "75") (name "unconnected-(U3-IO14-Pad22)") (class "Default")
      (node (ref "U3") (pin "22") (pinfunction "IO14_22") (pintype "bidirectional"))
    )
    (net (code "76") (name "unconnected-(U3-IO15-Pad8)") (class "Default")
      (node (ref "U3") (pin "8") (pinfunction "IO15_8") (pintype "bidirectional"))
    )
    (net (code "77") (name "unconnected-(U3-IO16-Pad9)") (class "Default")
      (node (ref "U3") (pin "9") (pinfunction "IO16_9") (pintype "bidirectional"))
    )
    (net (code "78") (name "unconnected-(U3-IO17-Pad10)") (class "Default")
      (node (ref "U3") (pin "10") (pinfunction "IO17_10") (pintype "bidirectional"))
    )
    (net (code "79") (name "unconnected-(U3-IO18-Pad11)") (class "Default")
      (node (ref "U3") (pin "11") (pinfunction "IO18_11") (pintype "bidirectional"))
    )
    (net (code "80") (name "unconnected-(U3-IO21-Pad23)") (class "Default")
      (node (ref "U3") (pin "23") (pinfunction "IO21_23") (pintype "bidirectional"))
    )
    (net (code "81") (name "unconnected-(U3-IO35-Pad28)") (class "Default")
      (node (ref "U3") (pin "28") (pinfunction "IO35_28") (pintype "bidirectional"))
    )
    (net (code "82") (name "unconnected-(U3-IO36-Pad29)") (class "Default")
      (node (ref "U3") (pin "29") (pinfunction "IO36_29") (pintype "bidirectional"))
    )
    (net (code "83") (name "unconnected-(U3-IO37-Pad30)") (class "Default")
      (node (ref "U3") (pin "30") (pinfunction "IO37_30") (pintype "bidirectional"))
    )
    (net (code "84") (name "unconnected-(U3-IO38-Pad31)") (class "Default")
      (node (ref "U3") (pin "31") (pinfunction "IO38_31") (pintype "bidirectional"))
    )
    (net (code "85") (name "unconnected-(U3-IO39-Pad32)") (class "Default")
      (node (ref "U3") (pin "32") (pinfunction "IO39_32") (pintype "bidirectional"))
    )
    (net (code "86") (name "unconnected-(U3-IO40-Pad33)") (class "Default")
      (node (ref "U3") (pin "33") (pinfunction "IO40_33") (pintype "bidirectional"))
    )
    (net (code "87") (name "unconnected-(U3-IO41-Pad34)") (class "Default")
      (node (ref "U3") (pin "34") (pinfunction "IO41_34") (pintype "bidirectional"))
    )
    (net (code "88") (name "unconnected-(U3-IO42-Pad35)") (class "Default")
      (node (ref "U3") (pin "35") (pinfunction "IO42_35") (pintype "bidirectional"))
    )
    (net (code "89") (name "unconnected-(U3-IO45-Pad26)") (class "Default")
      (node (ref "U3") (pin "26") (pinfunction "IO45_26") (pintype "bidirectional"))
    )
    (net (code "90") (name "unconnected-(U3-IO46-Pad16)") (class "Default")
      (node (ref "U3") (pin "16") (pinfunction "IO46_16") (pintype "bidirectional"))
    )
    (net (code "91") (name "unconnected-(U3-IO47-Pad24)") (class "Default")
      (node (ref "U3") (pin "24") (pinfunction "IO47_24") (pintype "bidirectional"))
    )
    (net (code "92") (name "unconnected-(U3-IO48-Pad25)") (class "Default")
      (node (ref "U3") (pin "25") (pinfunction "IO48_25") (pintype "bidirectional"))
    )
    (net (code "93") (name "unconnected-(U3-RXD0-Pad36)") (class "Default")
      (node (ref "U3") (pin "36") (pinfunction "RXD0_36") (pintype "bidirectional"))
    )
    (net (code "94") (name "unconnected-(U3-TXD0-Pad37)") (class "Default")
      (node (ref "U3") (pin "37") (pinfunction "TXD0_37") (pintype "bidirectional"))
    )
  )
)
